# M501B.net
KiCad netlist of a schematic drawn in EAGLE
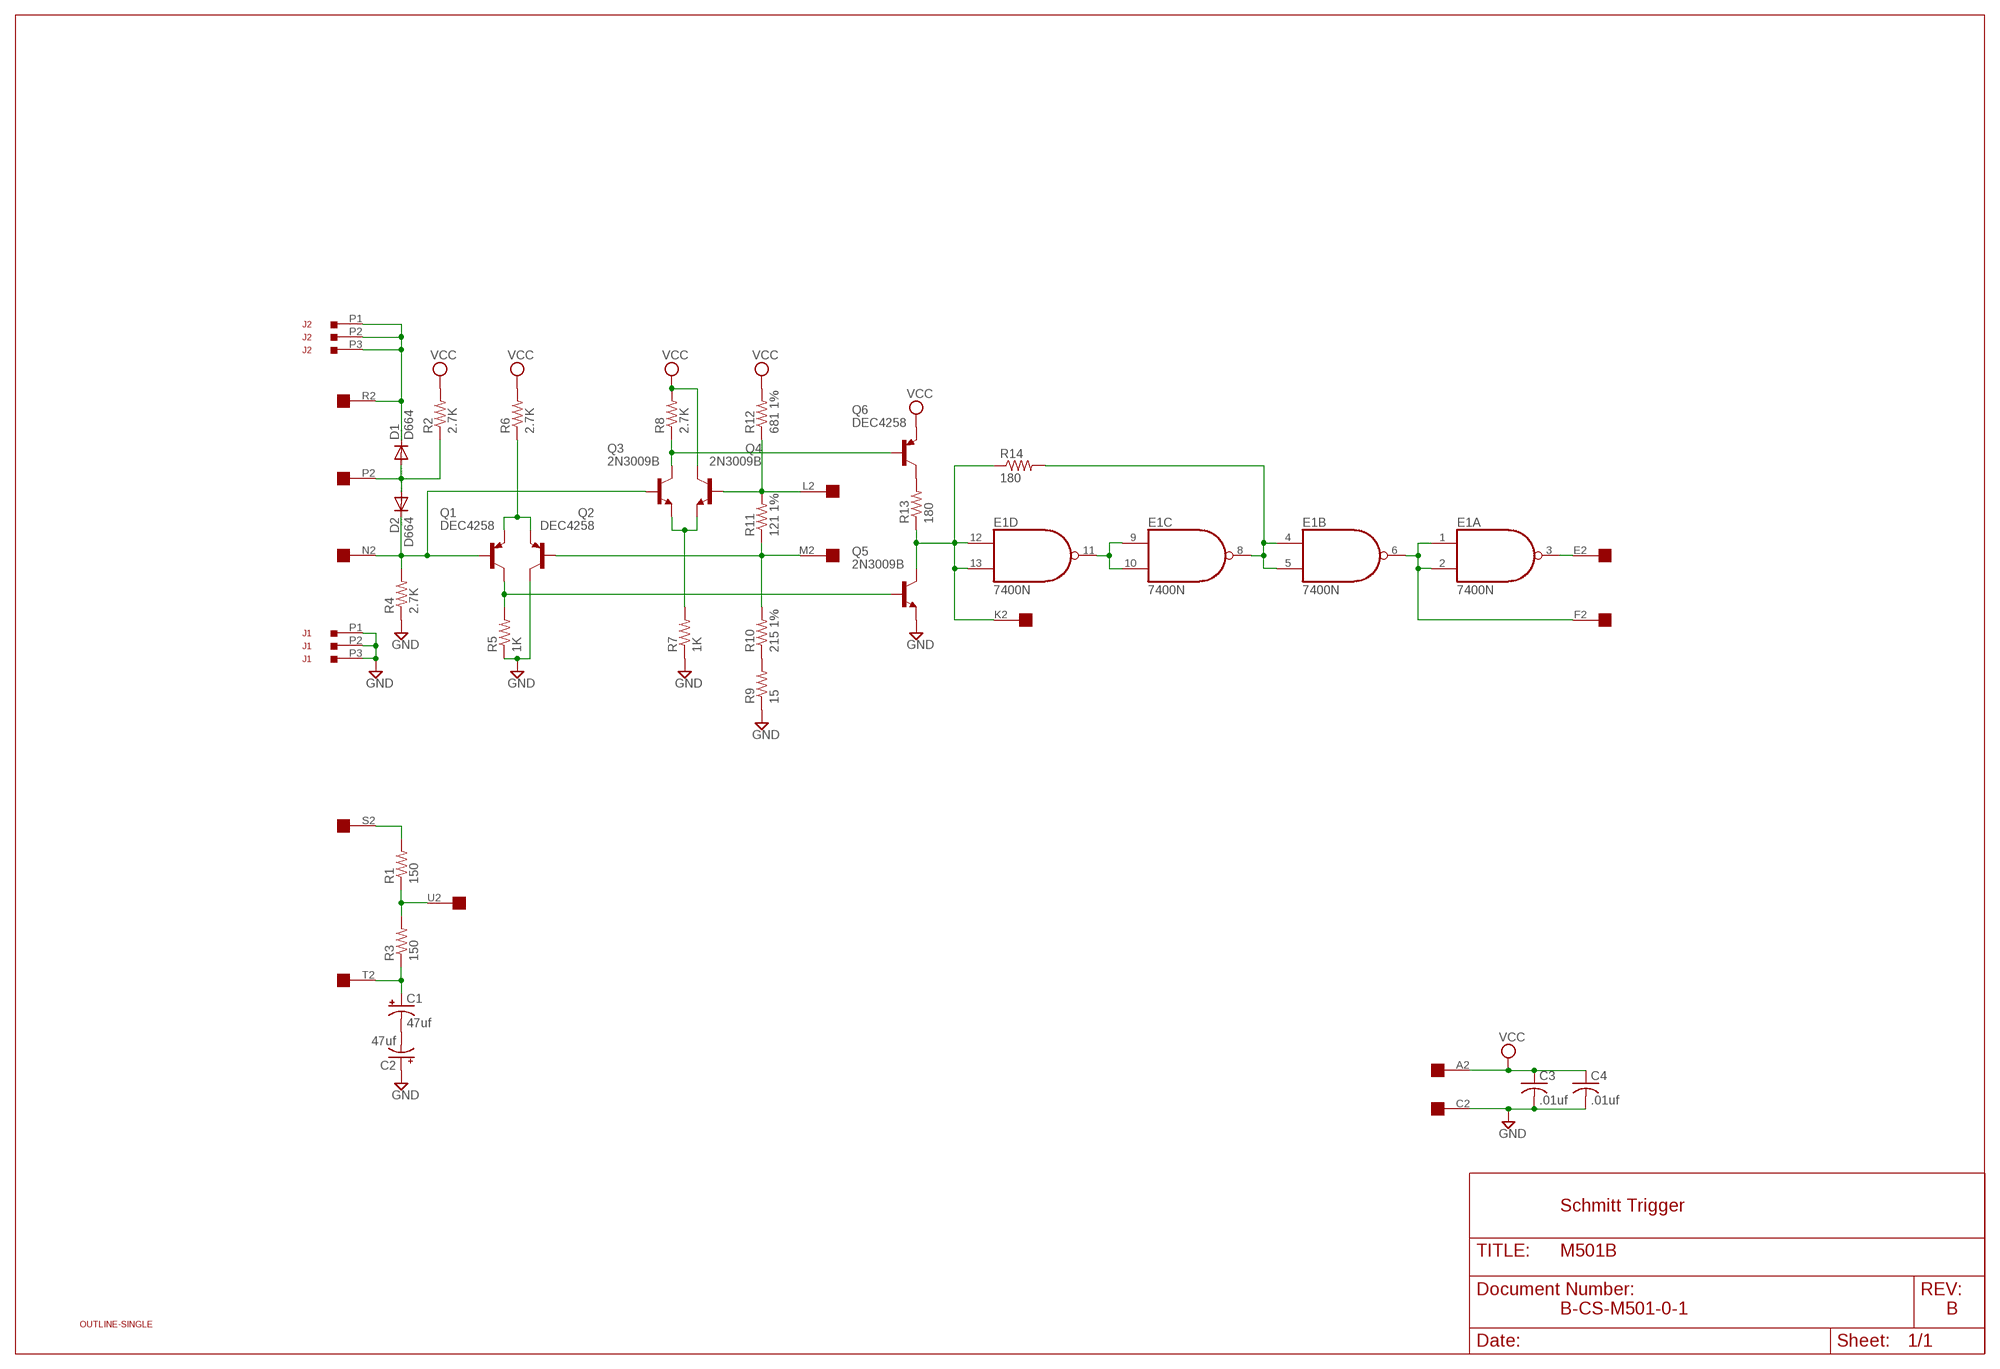
[diagram p0: schematic, sheet 1]

(export (version "E")
  (design (tool "Eeschema 10.0.6"))
  (components
    (comp (ref "C1")
      (value "47uf")
      (footprint "eagle-import:E22-6")
      (libsource (lib "eagle-import") (part "CPOL-USE22-6AXIAL"))
    )
    (comp (ref "C2")
      (value "47uf")
      (footprint "eagle-import:E22-6")
      (libsource (lib "eagle-import") (part "CPOL-USE22-6AXIAL"))
    )
    (comp (ref "C3")
      (value ".01uf")
      (footprint "eagle-import:C075-032X103")
      (libsource (lib "eagle-import") (part "C-US075-032X103"))
    )
    (comp (ref "C4")
      (value ".01uf")
      (footprint "eagle-import:C075-032X103")
      (libsource (lib "eagle-import") (part "C-US075-032X103"))
    )
    (comp (ref "D1")
      (value "D664")
      (footprint "eagle-import:DO35-10")
      (libsource (lib "eagle-import") (part "1N4148DO35-10"))
    )
    (comp (ref "D2")
      (value "D664")
      (footprint "eagle-import:DO35-10")
      (libsource (lib "eagle-import") (part "1N4148DO35-10"))
    )
    (comp (ref "E1")
      (value "7400N")
      (footprint "eagle-import:DIL14")
      (libsource (lib "eagle-import") (part "7400N"))
    )
    (comp (ref "J1")
      (value "34-22-1-03")
      (footprint "eagle-import:34-22-1-03")
      (libsource (lib "eagle-import") (part "34-22-1-03"))
    )
    (comp (ref "J2")
      (value "34-22-1-03")
      (footprint "eagle-import:34-22-1-03")
      (libsource (lib "eagle-import") (part "34-22-1-03"))
    )
    (comp (ref "Q1")
      (value "DEC4258")
      (footprint "eagle-import:TO39")
      (libsource (lib "eagle-import") (part "2N2904"))
    )
    (comp (ref "Q2")
      (value "DEC4258")
      (footprint "eagle-import:TO39")
      (libsource (lib "eagle-import") (part "2N2904"))
    )
    (comp (ref "Q3")
      (value "2N3009B")
      (footprint "eagle-import:TO39")
      (libsource (lib "eagle-import") (part "2N3019"))
    )
    (comp (ref "Q4")
      (value "2N3009B")
      (footprint "eagle-import:TO39")
      (libsource (lib "eagle-import") (part "2N3019"))
    )
    (comp (ref "Q5")
      (value "2N3009B")
      (footprint "eagle-import:TO39")
      (libsource (lib "eagle-import") (part "2N3019"))
    )
    (comp (ref "Q6")
      (value "DEC4258")
      (footprint "eagle-import:TO39")
      (libsource (lib "eagle-import") (part "2N2904"))
    )
    (comp (ref "R1")
      (value "150")
      (footprint "eagle-import:0207_10")
      (libsource (lib "eagle-import") (part "R-US_0207/10"))
    )
    (comp (ref "R2")
      (value "2.7K")
      (footprint "eagle-import:0207_10")
      (libsource (lib "eagle-import") (part "R-US_0207/10"))
    )
    (comp (ref "R3")
      (value "150")
      (footprint "eagle-import:0207_10")
      (libsource (lib "eagle-import") (part "R-US_0207/10"))
    )
    (comp (ref "R4")
      (value "2.7K")
      (footprint "eagle-import:0207_10")
      (libsource (lib "eagle-import") (part "R-US_0207/10"))
    )
    (comp (ref "R5")
      (value "1K")
      (footprint "eagle-import:0207_10")
      (libsource (lib "eagle-import") (part "R-US_0207/10"))
    )
    (comp (ref "R6")
      (value "2.7K")
      (footprint "eagle-import:0207_10")
      (libsource (lib "eagle-import") (part "R-US_0207/10"))
    )
    (comp (ref "R7")
      (value "1K")
      (footprint "eagle-import:0207_10")
      (libsource (lib "eagle-import") (part "R-US_0207/10"))
    )
    (comp (ref "R8")
      (value "2.7K")
      (footprint "eagle-import:0207_10")
      (libsource (lib "eagle-import") (part "R-US_0207/10"))
    )
    (comp (ref "R9")
      (value "15")
      (footprint "eagle-import:0207_10")
      (libsource (lib "eagle-import") (part "R-US_0207/10"))
    )
    (comp (ref "R10")
      (value "215 1%")
      (footprint "eagle-import:0207_15")
      (libsource (lib "eagle-import") (part "R-US_0207/15"))
    )
    (comp (ref "R11")
      (value "121 1%")
      (footprint "eagle-import:0207_15")
      (libsource (lib "eagle-import") (part "R-US_0207/15"))
    )
    (comp (ref "R12")
      (value "681 1%")
      (footprint "eagle-import:0207_15")
      (libsource (lib "eagle-import") (part "R-US_0207/15"))
    )
    (comp (ref "R13")
      (value "180")
      (footprint "eagle-import:0207_10")
      (libsource (lib "eagle-import") (part "R-US_0207/10"))
    )
    (comp (ref "R14")
      (value "180")
      (footprint "eagle-import:0207_10")
      (libsource (lib "eagle-import") (part "R-US_0207/10"))
    )
    (comp (ref "U$1")
      (value "EDGE-1")
      (footprint "eagle-import:EDGE-CON1")
      (libsource (lib "eagle-import") (part "EDGE-1"))
    )
    (comp (ref "U$4")
      (value "OUTLINE-SINGLE")
      (footprint "eagle-import:SINGLE")
      (libsource (lib "eagle-import") (part "OUTLINE-SINGLE"))
    )
  )
  (nets
    (net (code "1") (name "GND") (class "Default")
      (node (ref "C2") (pin "+") (pinfunction "+_+") (pintype "passive"))
      (node (ref "C3") (pin "2") (pinfunction "2_2") (pintype "passive"))
      (node (ref "C4") (pin "2") (pinfunction "2_2") (pintype "passive"))
      (node (ref "J1") (pin "P1") (pinfunction "P$2_P1") (pintype "bidirectional"))
      (node (ref "J1") (pin "P2") (pinfunction "P$2_P2") (pintype "bidirectional"))
      (node (ref "J1") (pin "P3") (pinfunction "P$2_P3") (pintype "bidirectional"))
      (node (ref "Q2") (pin "3") (pinfunction "C_3") (pintype "passive"))
      (node (ref "Q5") (pin "1") (pinfunction "E_1") (pintype "passive"))
      (node (ref "R4") (pin "1") (pinfunction "1_1") (pintype "passive"))
      (node (ref "R5") (pin "1") (pinfunction "1_1") (pintype "passive"))
      (node (ref "R7") (pin "1") (pinfunction "1_1") (pintype "passive"))
      (node (ref "R9") (pin "1") (pinfunction "1_1") (pintype "passive"))
      (node (ref "U$1") (pin "C2") (pinfunction "1_C2") (pintype "bidirectional"))
    )
    (net (code "2") (name "Net-(C1-Pad-)") (class "Default")
      (node (ref "C1") (pin "-") (pinfunction "-_-") (pintype "passive"))
      (node (ref "C2") (pin "-") (pinfunction "-_-") (pintype "passive"))
    )
    (net (code "3") (name "Net-(E1A-I0)") (class "Default")
      (node (ref "E1") (pin "1") (pinfunction "I0_1") (pintype "input"))
      (node (ref "E1") (pin "2") (pinfunction "I1_2") (pintype "input"))
      (node (ref "E1") (pin "6") (pinfunction "O_6") (pintype "output"))
      (node (ref "U$1") (pin "F2") (pinfunction "1_F2") (pintype "bidirectional"))
    )
    (net (code "4") (name "Net-(E1A-O)") (class "Default")
      (node (ref "E1") (pin "3") (pinfunction "O_3") (pintype "output"))
      (node (ref "U$1") (pin "E2") (pinfunction "1_E2") (pintype "bidirectional"))
    )
    (net (code "5") (name "Net-(E1B-I0)") (class "Default")
      (node (ref "E1") (pin "4") (pinfunction "I0_4") (pintype "input"))
      (node (ref "E1") (pin "5") (pinfunction "I1_5") (pintype "input"))
      (node (ref "E1") (pin "8") (pinfunction "O_8") (pintype "output"))
      (node (ref "R14") (pin "2") (pinfunction "2_2") (pintype "passive"))
    )
    (net (code "6") (name "Net-(E1C-I0)") (class "Default")
      (node (ref "E1") (pin "10") (pinfunction "I1_10") (pintype "input"))
      (node (ref "E1") (pin "11") (pinfunction "O_11") (pintype "output"))
      (node (ref "E1") (pin "9") (pinfunction "I0_9") (pintype "input"))
    )
    (net (code "7") (name "Net-(E1D-I0)") (class "Default")
      (node (ref "E1") (pin "12") (pinfunction "I0_12") (pintype "input"))
      (node (ref "E1") (pin "13") (pinfunction "I1_13") (pintype "input"))
      (node (ref "Q5") (pin "3") (pinfunction "C_3") (pintype "passive"))
      (node (ref "R13") (pin "1") (pinfunction "1_1") (pintype "passive"))
      (node (ref "R14") (pin "1") (pinfunction "1_1") (pintype "passive"))
      (node (ref "U$1") (pin "K2") (pinfunction "1_K2") (pintype "bidirectional"))
    )
    (net (code "8") (name "Net-(J2A-P$2)") (class "Default")
      (node (ref "D1") (pin "C") (pinfunction "C_C") (pintype "passive"))
      (node (ref "J2") (pin "P1") (pinfunction "P$2_P1") (pintype "bidirectional"))
      (node (ref "J2") (pin "P2") (pinfunction "P$2_P2") (pintype "bidirectional"))
      (node (ref "J2") (pin "P3") (pinfunction "P$2_P3") (pintype "bidirectional"))
      (node (ref "U$1") (pin "R2") (pinfunction "1_R2") (pintype "bidirectional"))
    )
    (net (code "9") (name "Net-(Q1-B)") (class "Default")
      (node (ref "D2") (pin "C") (pinfunction "C_C") (pintype "passive"))
      (node (ref "Q1") (pin "2") (pinfunction "B_2") (pintype "passive"))
      (node (ref "Q3") (pin "2") (pinfunction "B_2") (pintype "passive"))
      (node (ref "R4") (pin "2") (pinfunction "2_2") (pintype "passive"))
      (node (ref "U$1") (pin "N2") (pinfunction "1_N2") (pintype "bidirectional"))
    )
    (net (code "10") (name "Net-(Q1-C)") (class "Default")
      (node (ref "Q1") (pin "3") (pinfunction "C_3") (pintype "passive"))
      (node (ref "Q5") (pin "2") (pinfunction "B_2") (pintype "passive"))
      (node (ref "R5") (pin "2") (pinfunction "2_2") (pintype "passive"))
    )
    (net (code "11") (name "Net-(Q1-E)") (class "Default")
      (node (ref "Q1") (pin "1") (pinfunction "E_1") (pintype "passive"))
      (node (ref "Q2") (pin "1") (pinfunction "E_1") (pintype "passive"))
      (node (ref "R6") (pin "1") (pinfunction "1_1") (pintype "passive"))
    )
    (net (code "12") (name "Net-(Q2-B)") (class "Default")
      (node (ref "Q2") (pin "2") (pinfunction "B_2") (pintype "passive"))
      (node (ref "R10") (pin "2") (pinfunction "2_2") (pintype "passive"))
      (node (ref "R11") (pin "1") (pinfunction "1_1") (pintype "passive"))
      (node (ref "U$1") (pin "M2") (pinfunction "1_M2") (pintype "bidirectional"))
    )
    (net (code "13") (name "Net-(Q3-C)") (class "Default")
      (node (ref "Q3") (pin "3") (pinfunction "C_3") (pintype "passive"))
      (node (ref "Q6") (pin "2") (pinfunction "B_2") (pintype "passive"))
      (node (ref "R8") (pin "1") (pinfunction "1_1") (pintype "passive"))
    )
    (net (code "14") (name "Net-(Q3-E)") (class "Default")
      (node (ref "Q3") (pin "1") (pinfunction "E_1") (pintype "passive"))
      (node (ref "Q4") (pin "1") (pinfunction "E_1") (pintype "passive"))
      (node (ref "R7") (pin "2") (pinfunction "2_2") (pintype "passive"))
    )
    (net (code "15") (name "Net-(Q4-B)") (class "Default")
      (node (ref "Q4") (pin "2") (pinfunction "B_2") (pintype "passive"))
      (node (ref "R11") (pin "2") (pinfunction "2_2") (pintype "passive"))
      (node (ref "R12") (pin "1") (pinfunction "1_1") (pintype "passive"))
      (node (ref "U$1") (pin "L2") (pinfunction "1_L2") (pintype "bidirectional"))
    )
    (net (code "16") (name "Net-(Q6-C)") (class "Default")
      (node (ref "Q6") (pin "3") (pinfunction "C_3") (pintype "passive"))
      (node (ref "R13") (pin "2") (pinfunction "2_2") (pintype "passive"))
    )
    (net (code "17") (name "Net-(R10-Pad1)") (class "Default")
      (node (ref "R10") (pin "1") (pinfunction "1_1") (pintype "passive"))
      (node (ref "R9") (pin "2") (pinfunction "2_2") (pintype "passive"))
    )
    (net (code "18") (name "Net-(U$1M-1)") (class "Default")
      (node (ref "D1") (pin "A") (pinfunction "A_A") (pintype "passive"))
      (node (ref "D2") (pin "A") (pinfunction "A_A") (pintype "passive"))
      (node (ref "R2") (pin "1") (pinfunction "1_1") (pintype "passive"))
      (node (ref "U$1") (pin "P2") (pinfunction "1_P2") (pintype "bidirectional"))
    )
    (net (code "19") (name "Net-(U$1O-1)") (class "Default")
      (node (ref "R1") (pin "2") (pinfunction "2_2") (pintype "passive"))
      (node (ref "U$1") (pin "S2") (pinfunction "1_S2") (pintype "bidirectional"))
    )
    (net (code "20") (name "Net-(U$1P-1)") (class "Default")
      (node (ref "C1") (pin "+") (pinfunction "+_+") (pintype "passive"))
      (node (ref "R3") (pin "1") (pinfunction "1_1") (pintype "passive"))
      (node (ref "U$1") (pin "T2") (pinfunction "1_T2") (pintype "bidirectional"))
    )
    (net (code "21") (name "Net-(U$1Q-1)") (class "Default")
      (node (ref "R1") (pin "1") (pinfunction "1_1") (pintype "passive"))
      (node (ref "R3") (pin "2") (pinfunction "2_2") (pintype "passive"))
      (node (ref "U$1") (pin "U2") (pinfunction "1_U2") (pintype "bidirectional"))
    )
    (net (code "22") (name "VCC") (class "Default")
      (node (ref "C3") (pin "1") (pinfunction "1_1") (pintype "passive"))
      (node (ref "C4") (pin "1") (pinfunction "1_1") (pintype "passive"))
      (node (ref "Q4") (pin "3") (pinfunction "C_3") (pintype "passive"))
      (node (ref "Q6") (pin "1") (pinfunction "E_1") (pintype "passive"))
      (node (ref "R12") (pin "2") (pinfunction "2_2") (pintype "passive"))
      (node (ref "R2") (pin "2") (pinfunction "2_2") (pintype "passive"))
      (node (ref "R6") (pin "2") (pinfunction "2_2") (pintype "passive"))
      (node (ref "R8") (pin "2") (pinfunction "2_2") (pintype "passive"))
      (node (ref "U$1") (pin "A2") (pinfunction "1_A2") (pintype "bidirectional"))
    )
  )
)
